# Schema-ruche.net
KiCad netlist of a schematic drawn in Altium Designer
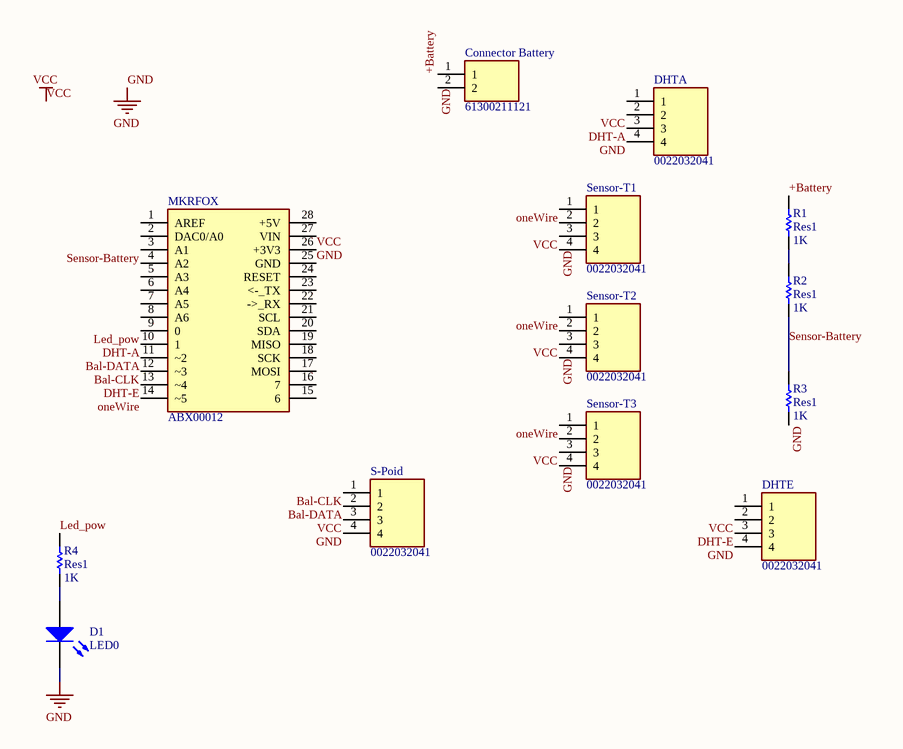
[diagram p0: Schema-ruche.SchDoc]

(export (version "E")
  (design (tool "Eeschema 10.0.6"))
  (components
    (comp (ref "Connector Battery")
      (value "61300211121")
      (footprint "SamacSys:HDRV2W110P0X254_1X2_508X254X854P")
      (description "Connector")
      (fields (field (name "MOUSER PART NUMBER") "710-61300211121"))
      (libsource (lib "SamacSys") (part "61300211121"))
    )
    (comp (ref "D1")
      (value "LED0")
      (footprint "LED-0")
      (description "Typical INFRARED GaAs LED")
      (fields (field (name "PUBLISHER") "Altium Limited"))
      (libsource (lib "Miscellaneous Devices") (part "LED0"))
    )
    (comp (ref "DHTA")
      (value "0022032041")
      (footprint "SamacSys:HDRV4W87P0X254_1X4_991X236X1155P")
      (description "Connector")
      (libsource (lib "SamacSys") (part "0022032041"))
    )
    (comp (ref "DHTE")
      (value "0022032041")
      (footprint "SamacSys:HDRV4W87P0X254_1X4_991X236X1155P")
      (description "Connector")
      (libsource (lib "SamacSys") (part "0022032041"))
    )
    (comp (ref "MKRFOX")
      (value "ABX00012")
      (footprint "SamacSys:ABX00012")
      (description "Undefined or Miscellaneous")
      (fields (field (name "MOUSER PART NUMBER") "782-ABX00012"))
      (libsource (lib "SamacSys") (part "ABX00012"))
    )
    (comp (ref "R1")
      (value "Res1")
      (footprint "AXIAL-0.3")
      (description "Resistor")
      (fields (field (name "ALTIUM_VALUE") "1K") (field (name "PUBLISHER") "Altium Limited"))
      (libsource (lib "Miscellaneous Devices") (part "Res1"))
    )
    (comp (ref "R2")
      (value "Res1")
      (footprint "AXIAL-0.3")
      (description "Resistor")
      (fields (field (name "ALTIUM_VALUE") "1K") (field (name "PUBLISHER") "Altium Limited"))
      (libsource (lib "Miscellaneous Devices") (part "Res1"))
    )
    (comp (ref "R3")
      (value "Res1")
      (footprint "AXIAL-0.3")
      (description "Resistor")
      (fields (field (name "ALTIUM_VALUE") "1K") (field (name "PUBLISHER") "Altium Limited"))
      (libsource (lib "Miscellaneous Devices") (part "Res1"))
    )
    (comp (ref "R4")
      (value "Res1")
      (footprint "AXIAL-0.3")
      (description "Resistor")
      (fields (field (name "ALTIUM_VALUE") "1K") (field (name "PUBLISHER") "Altium Limited"))
      (libsource (lib "Miscellaneous Devices") (part "Res1"))
    )
    (comp (ref "S-Poid")
      (value "0022032041")
      (footprint "SamacSys:HDRV4W87P0X254_1X4_991X236X1155P")
      (description "Connector")
      (libsource (lib "SamacSys") (part "0022032041"))
    )
    (comp (ref "Sensor-T1")
      (value "0022032041")
      (footprint "SamacSys:HDRV4W87P0X254_1X4_991X236X1155P")
      (description "Connector")
      (libsource (lib "SamacSys") (part "0022032041"))
    )
    (comp (ref "Sensor-T2")
      (value "0022032041")
      (footprint "SamacSys:HDRV4W87P0X254_1X4_991X236X1155P")
      (description "Connector")
      (libsource (lib "SamacSys") (part "0022032041"))
    )
    (comp (ref "Sensor-T3")
      (value "0022032041")
      (footprint "SamacSys:HDRV4W87P0X254_1X4_991X236X1155P")
      (description "Connector")
      (libsource (lib "SamacSys") (part "0022032041"))
    )
  )
  (nets
    (net (code "1") (name "/+Battery") (class "Default")
      (node (ref "Connector Battery") (pin "1") (pinfunction "1_1") (pintype "passive"))
      (node (ref "R1") (pin "2") (pinfunction "2_2") (pintype "passive"))
    )
    (net (code "2") (name "/Bal-CLK") (class "Default")
      (node (ref "MKRFOX") (pin "12") (pinfunction "~3_12") (pintype "passive"))
      (node (ref "S-Poid") (pin "1") (pinfunction "1_1") (pintype "passive"))
    )
    (net (code "3") (name "/Bal-DATA") (class "Default")
      (node (ref "MKRFOX") (pin "11") (pinfunction "~2_11") (pintype "passive"))
      (node (ref "S-Poid") (pin "2") (pinfunction "2_2") (pintype "passive"))
    )
    (net (code "4") (name "/DHT-A") (class "Default")
      (node (ref "DHTA") (pin "3") (pinfunction "3_3") (pintype "passive"))
      (node (ref "MKRFOX") (pin "10") (pinfunction "1_10") (pintype "passive"))
    )
    (net (code "5") (name "/DHT-E") (class "Default")
      (node (ref "DHTE") (pin "3") (pinfunction "3_3") (pintype "passive"))
      (node (ref "MKRFOX") (pin "13") (pinfunction "~4_13") (pintype "passive"))
    )
    (net (code "6") (name "/Led_pow") (class "Default")
      (node (ref "MKRFOX") (pin "9") (pinfunction "0_9") (pintype "passive"))
      (node (ref "R4") (pin "2") (pinfunction "2_2") (pintype "passive"))
    )
    (net (code "7") (name "/Sensor-Battery") (class "Default")
      (node (ref "MKRFOX") (pin "3") (pinfunction "A1_3") (pintype "passive"))
      (node (ref "R2") (pin "1") (pinfunction "1_1") (pintype "passive"))
      (node (ref "R3") (pin "2") (pinfunction "2_2") (pintype "passive"))
    )
    (net (code "8") (name "/oneWire") (class "Default")
      (node (ref "MKRFOX") (pin "14") (pinfunction "~5_14") (pintype "passive"))
      (node (ref "Sensor-T1") (pin "1") (pinfunction "1_1") (pintype "passive"))
      (node (ref "Sensor-T2") (pin "1") (pinfunction "1_1") (pintype "passive"))
      (node (ref "Sensor-T3") (pin "1") (pinfunction "1_1") (pintype "passive"))
    )
    (net (code "9") (name "GND") (class "Default")
      (node (ref "Connector Battery") (pin "2") (pinfunction "2_2") (pintype "passive"))
      (node (ref "D1") (pin "2") (pinfunction "K_2") (pintype "passive"))
      (node (ref "DHTA") (pin "4") (pinfunction "4_4") (pintype "passive"))
      (node (ref "DHTE") (pin "4") (pinfunction "4_4") (pintype "passive"))
      (node (ref "MKRFOX") (pin "25") (pinfunction "GND_25") (pintype "passive"))
      (node (ref "R3") (pin "1") (pinfunction "1_1") (pintype "passive"))
      (node (ref "S-Poid") (pin "4") (pinfunction "4_4") (pintype "passive"))
      (node (ref "Sensor-T1") (pin "4") (pinfunction "4_4") (pintype "passive"))
      (node (ref "Sensor-T2") (pin "4") (pinfunction "4_4") (pintype "passive"))
      (node (ref "Sensor-T3") (pin "4") (pinfunction "4_4") (pintype "passive"))
    )
    (net (code "10") (name "Net-(D1-A)") (class "Default")
      (node (ref "D1") (pin "1") (pinfunction "A_1") (pintype "passive"))
      (node (ref "R4") (pin "1") (pinfunction "1_1") (pintype "passive"))
    )
    (net (code "11") (name "Net-(R1-Pad1)") (class "Default")
      (node (ref "R1") (pin "1") (pinfunction "1_1") (pintype "passive"))
      (node (ref "R2") (pin "2") (pinfunction "2_2") (pintype "passive"))
    )
    (net (code "12") (name "VCC") (class "Default")
      (node (ref "DHTA") (pin "2") (pinfunction "2_2") (pintype "passive"))
      (node (ref "DHTE") (pin "2") (pinfunction "2_2") (pintype "passive"))
      (node (ref "MKRFOX") (pin "26") (pinfunction "+3V3_26") (pintype "passive"))
      (node (ref "S-Poid") (pin "3") (pinfunction "3_3") (pintype "passive"))
      (node (ref "Sensor-T1") (pin "3") (pinfunction "3_3") (pintype "passive"))
      (node (ref "Sensor-T2") (pin "3") (pinfunction "3_3") (pintype "passive"))
      (node (ref "Sensor-T3") (pin "3") (pinfunction "3_3") (pintype "passive"))
    )
    (net (code "13") (name "unconnected-(DHTA-Pad1)") (class "Default")
      (node (ref "DHTA") (pin "1") (pinfunction "1_1") (pintype "passive"))
    )
    (net (code "14") (name "unconnected-(DHTE-Pad1)") (class "Default")
      (node (ref "DHTE") (pin "1") (pinfunction "1_1") (pintype "passive"))
    )
    (net (code "15") (name "unconnected-(MKRFOX-+5V-Pad28)") (class "Default")
      (node (ref "MKRFOX") (pin "28") (pinfunction "+5V_28") (pintype "passive"))
    )
    (net (code "16") (name "unconnected-(MKRFOX-->_RX-Pad22)") (class "Default")
      (node (ref "MKRFOX") (pin "22") (pinfunction "->_RX_22") (pintype "passive"))
    )
    (net (code "17") (name "unconnected-(MKRFOX-6-Pad15)") (class "Default")
      (node (ref "MKRFOX") (pin "15") (pinfunction "6_15") (pintype "passive"))
    )
    (net (code "18") (name "unconnected-(MKRFOX-7-Pad16)") (class "Default")
      (node (ref "MKRFOX") (pin "16") (pinfunction "7_16") (pintype "passive"))
    )
    (net (code "19") (name "unconnected-(MKRFOX-<-_TX-Pad23)") (class "Default")
      (node (ref "MKRFOX") (pin "23") (pinfunction "<-_TX_23") (pintype "passive"))
    )
    (net (code "20") (name "unconnected-(MKRFOX-A2-Pad4)") (class "Default")
      (node (ref "MKRFOX") (pin "4") (pinfunction "A2_4") (pintype "passive"))
    )
    (net (code "21") (name "unconnected-(MKRFOX-A3-Pad5)") (class "Default")
      (node (ref "MKRFOX") (pin "5") (pinfunction "A3_5") (pintype "passive"))
    )
    (net (code "22") (name "unconnected-(MKRFOX-A4-Pad6)") (class "Default")
      (node (ref "MKRFOX") (pin "6") (pinfunction "A4_6") (pintype "passive"))
    )
    (net (code "23") (name "unconnected-(MKRFOX-A5-Pad7)") (class "Default")
      (node (ref "MKRFOX") (pin "7") (pinfunction "A5_7") (pintype "passive"))
    )
    (net (code "24") (name "unconnected-(MKRFOX-A6-Pad8)") (class "Default")
      (node (ref "MKRFOX") (pin "8") (pinfunction "A6_8") (pintype "passive"))
    )
    (net (code "25") (name "unconnected-(MKRFOX-AREF-Pad1)") (class "Default")
      (node (ref "MKRFOX") (pin "1") (pinfunction "AREF_1") (pintype "passive"))
    )
    (net (code "26") (name "unconnected-(MKRFOX-DAC0{slash}A0-Pad2)") (class "Default")
      (node (ref "MKRFOX") (pin "2") (pinfunction "DAC0/A0_2") (pintype "passive"))
    )
    (net (code "27") (name "unconnected-(MKRFOX-MISO-Pad19)") (class "Default")
      (node (ref "MKRFOX") (pin "19") (pinfunction "MISO_19") (pintype "passive"))
    )
    (net (code "28") (name "unconnected-(MKRFOX-MOSI-Pad17)") (class "Default")
      (node (ref "MKRFOX") (pin "17") (pinfunction "MOSI_17") (pintype "passive"))
    )
    (net (code "29") (name "unconnected-(MKRFOX-RESET-Pad24)") (class "Default")
      (node (ref "MKRFOX") (pin "24") (pinfunction "RESET_24") (pintype "passive"))
    )
    (net (code "30") (name "unconnected-(MKRFOX-SCK-Pad18)") (class "Default")
      (node (ref "MKRFOX") (pin "18") (pinfunction "SCK_18") (pintype "passive"))
    )
    (net (code "31") (name "unconnected-(MKRFOX-SCL-Pad21)") (class "Default")
      (node (ref "MKRFOX") (pin "21") (pinfunction "SCL_21") (pintype "passive"))
    )
    (net (code "32") (name "unconnected-(MKRFOX-SDA-Pad20)") (class "Default")
      (node (ref "MKRFOX") (pin "20") (pinfunction "SDA_20") (pintype "passive"))
    )
    (net (code "33") (name "unconnected-(MKRFOX-VIN-Pad27)") (class "Default")
      (node (ref "MKRFOX") (pin "27") (pinfunction "VIN_27") (pintype "passive"))
    )
    (net (code "34") (name "unconnected-(Sensor-T1-Pad2)") (class "Default")
      (node (ref "Sensor-T1") (pin "2") (pinfunction "2_2") (pintype "passive"))
    )
    (net (code "35") (name "unconnected-(Sensor-T2-Pad2)") (class "Default")
      (node (ref "Sensor-T2") (pin "2") (pinfunction "2_2") (pintype "passive"))
    )
    (net (code "36") (name "unconnected-(Sensor-T3-Pad2)") (class "Default")
      (node (ref "Sensor-T3") (pin "2") (pinfunction "2_2") (pintype "passive"))
    )
  )
)
